# PowerSocket.net
KiCad netlist of a schematic drawn in EAGLE
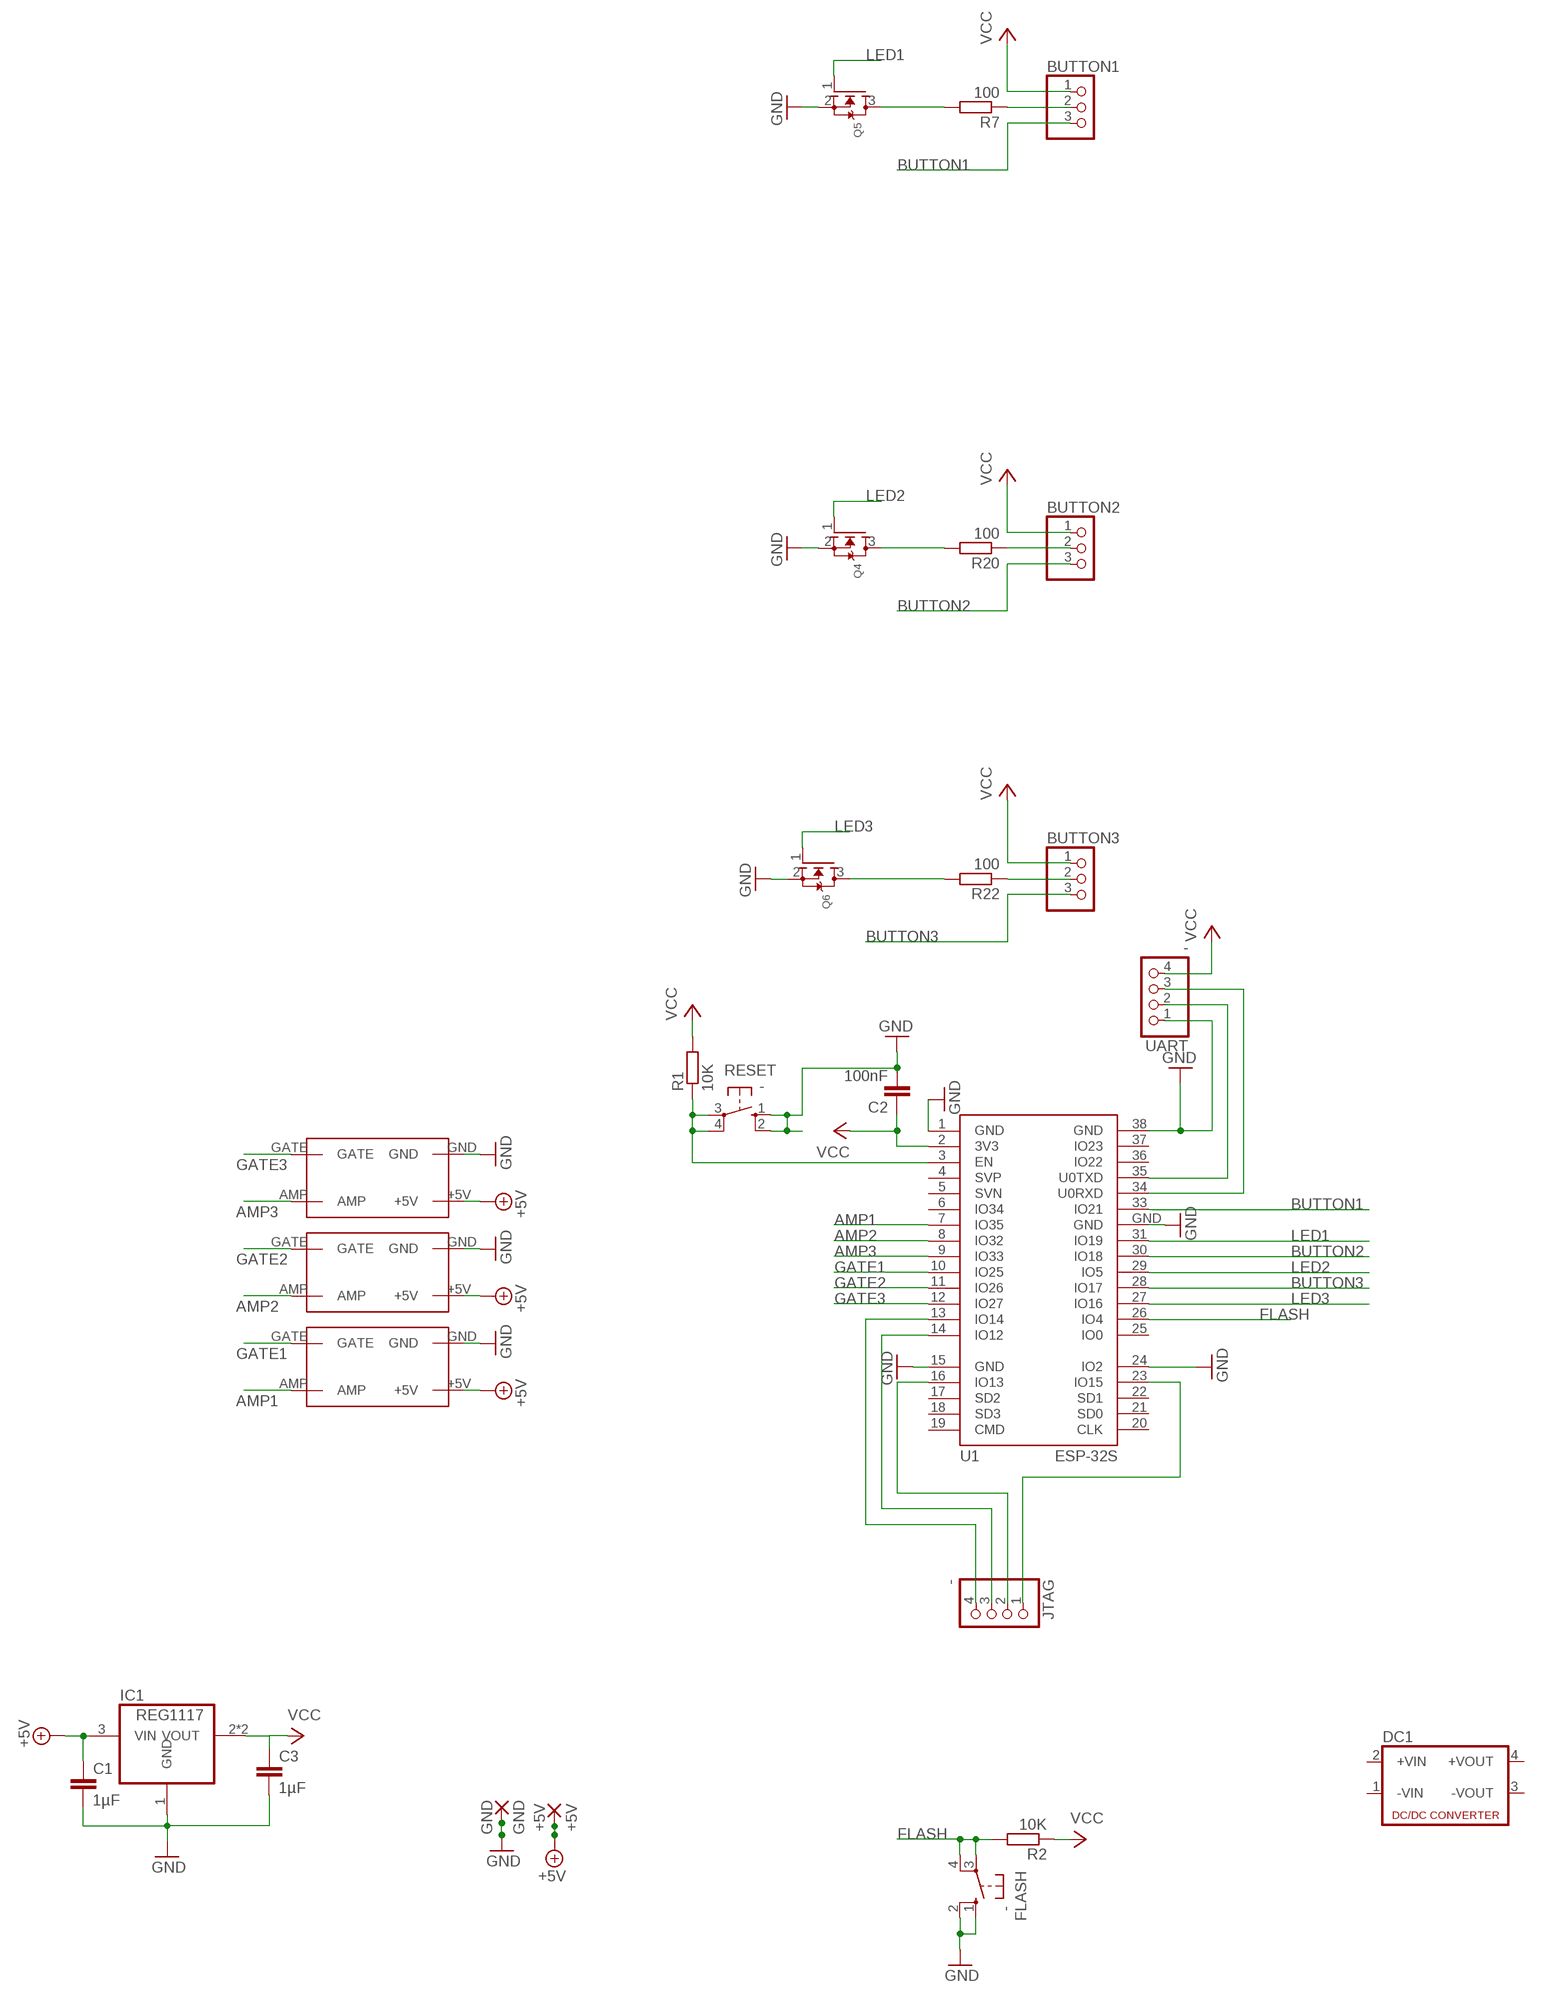
[diagram p0: schematic, sheet 1]

(export (version "E")
  (design (tool "Eeschema 10.0.6"))
  (components
    (comp (ref "+5V")
      (value "+5V")
      (footprint "eagle-import:2,15_1,0")
      (libsource (lib "eagle-import") (part "2,15/1,0"))
    )
    (comp (ref "BUTTON1")
      (value "PINHD-1X3")
      (footprint "eagle-import:1X03")
      (libsource (lib "eagle-import") (part "PINHD-1X3"))
    )
    (comp (ref "BUTTON2")
      (value "PINHD-1X3")
      (footprint "eagle-import:1X03")
      (libsource (lib "eagle-import") (part "PINHD-1X3"))
    )
    (comp (ref "BUTTON3")
      (value "PINHD-1X3")
      (footprint "eagle-import:1X03")
      (libsource (lib "eagle-import") (part "PINHD-1X3"))
    )
    (comp (ref "C1")
      (value "1µF")
      (footprint "eagle-import:C025-024X044")
      (libsource (lib "eagle-import") (part "C-EU025-024X044"))
    )
    (comp (ref "C2")
      (value "100nF")
      (footprint "eagle-import:C1206")
      (libsource (lib "eagle-import") (part "C-EUC1206"))
    )
    (comp (ref "C3")
      (value "1µF")
      (footprint "eagle-import:C025-024X044")
      (libsource (lib "eagle-import") (part "C-EU025-024X044"))
    )
    (comp (ref "DC1")
      (value "NME")
      (footprint "eagle-import:NME")
      (fields (field (name "MF") "C & D TECHNOLOGIES, INC") (field (name "MPN") "NME1205D"))
      (libsource (lib "eagle-import") (part "NME"))
    )
    (comp (ref "FLASH")
      (value "-")
      (footprint "eagle-import:B3F-10XX")
      (fields (field (name "MPN") "B3F-1000"))
      (libsource (lib "eagle-import") (part "10-XX"))
    )
    (comp (ref "GND")
      (value "GND")
      (footprint "eagle-import:2,15_1,0")
      (libsource (lib "eagle-import") (part "2,15/1,0"))
    )
    (comp (ref "IC1")
      (value "REG1117")
      (footprint "eagle-import:SOT223")
      (libsource (lib "eagle-import") (part "REG1117"))
    )
    (comp (ref "JTAG")
      (value "-")
      (footprint "eagle-import:1X04")
      (libsource (lib "eagle-import") (part "PINHD-1X4"))
    )
    (comp (ref "Q4")
      (value "MOSFET-NREFLOW")
      (footprint "eagle-import:SOT23")
      (libsource (lib "eagle-import") (part "MOSFET-NREFLOW"))
    )
    (comp (ref "Q5")
      (value "MOSFET-NREFLOW")
      (footprint "eagle-import:SOT23")
      (libsource (lib "eagle-import") (part "MOSFET-NREFLOW"))
    )
    (comp (ref "Q6")
      (value "MOSFET-NREFLOW")
      (footprint "eagle-import:SOT23")
      (libsource (lib "eagle-import") (part "MOSFET-NREFLOW"))
    )
    (comp (ref "R1")
      (value "10K")
      (footprint "eagle-import:R0805")
      (libsource (lib "eagle-import") (part "R-EU_R0805"))
    )
    (comp (ref "R2")
      (value "10K")
      (footprint "eagle-import:R0805")
      (libsource (lib "eagle-import") (part "R-EU_R0805"))
    )
    (comp (ref "R7")
      (value "100")
      (footprint "eagle-import:R0805")
      (libsource (lib "eagle-import") (part "R-EU_R0805"))
    )
    (comp (ref "R20")
      (value "100")
      (footprint "eagle-import:R0805")
      (libsource (lib "eagle-import") (part "R-EU_R0805"))
    )
    (comp (ref "R22")
      (value "100")
      (footprint "eagle-import:R0805")
      (libsource (lib "eagle-import") (part "R-EU_R0805"))
    )
    (comp (ref "RESET")
      (value "-")
      (footprint "eagle-import:B3F-10XX")
      (fields (field (name "MPN") "B3F-1000"))
      (libsource (lib "eagle-import") (part "10-XX"))
    )
    (comp (ref "U$2")
      (value "RELAY_BOARD")
      (footprint "eagle-import:RELAY_BOARD")
      (libsource (lib "eagle-import") (part "RELAY_BOARD"))
    )
    (comp (ref "U$3")
      (value "RELAY_BOARD")
      (footprint "eagle-import:RELAY_BOARD")
      (libsource (lib "eagle-import") (part "RELAY_BOARD"))
    )
    (comp (ref "U$4")
      (value "RELAY_BOARD")
      (footprint "eagle-import:RELAY_BOARD")
      (libsource (lib "eagle-import") (part "RELAY_BOARD"))
    )
    (comp (ref "U1")
      (value "ESP-32S")
      (footprint "eagle-import:ESP-32S")
      (libsource (lib "eagle-import") (part "ESP-32S"))
    )
    (comp (ref "UART")
      (value "-")
      (footprint "eagle-import:1X04")
      (libsource (lib "eagle-import") (part "PINHD-1X4"))
    )
  )
  (nets
    (net (code "1") (name "+5V") (class "Default")
      (node (ref "+5V") (pin "1") (pinfunction "P_1") (pintype "passive"))
      (node (ref "C1") (pin "1") (pinfunction "1_1") (pintype "passive"))
      (node (ref "IC1") (pin "3") (pinfunction "VIN_3") (pintype "input"))
      (node (ref "U$2") (pin "+5V") (pinfunction "+5V_+5V") (pintype "power_in"))
      (node (ref "U$3") (pin "+5V") (pinfunction "+5V_+5V") (pintype "power_in"))
      (node (ref "U$4") (pin "+5V") (pinfunction "+5V_+5V") (pintype "power_in"))
    )
    (net (code "2") (name "/AMP1") (class "Default")
      (node (ref "U$4") (pin "AMP") (pinfunction "AMP_AMP") (pintype "output"))
      (node (ref "U1") (pin "7") (pinfunction "IO35_7") (pintype "bidirectional"))
    )
    (net (code "3") (name "/AMP2") (class "Default")
      (node (ref "U$3") (pin "AMP") (pinfunction "AMP_AMP") (pintype "output"))
      (node (ref "U1") (pin "8") (pinfunction "IO32_8") (pintype "bidirectional"))
    )
    (net (code "4") (name "/AMP3") (class "Default")
      (node (ref "U$2") (pin "AMP") (pinfunction "AMP_AMP") (pintype "output"))
      (node (ref "U1") (pin "9") (pinfunction "IO33_9") (pintype "bidirectional"))
    )
    (net (code "5") (name "/BUTTON1") (class "Default")
      (node (ref "BUTTON1") (pin "3") (pinfunction "3_3") (pintype "passive"))
      (node (ref "U1") (pin "33") (pinfunction "IO21_33") (pintype "bidirectional"))
    )
    (net (code "6") (name "/BUTTON2") (class "Default")
      (node (ref "BUTTON2") (pin "3") (pinfunction "3_3") (pintype "passive"))
      (node (ref "U1") (pin "30") (pinfunction "IO18_30") (pintype "bidirectional"))
    )
    (net (code "7") (name "/BUTTON3") (class "Default")
      (node (ref "BUTTON3") (pin "3") (pinfunction "3_3") (pintype "passive"))
      (node (ref "U1") (pin "28") (pinfunction "IO17_28") (pintype "bidirectional"))
    )
    (net (code "8") (name "/FLASH") (class "Default")
      (node (ref "FLASH") (pin "3") (pinfunction "P_3") (pintype "passive"))
      (node (ref "FLASH") (pin "4") (pinfunction "P1_4") (pintype "passive"))
      (node (ref "R2") (pin "2") (pinfunction "2_2") (pintype "passive"))
      (node (ref "U1") (pin "26") (pinfunction "IO4_26") (pintype "bidirectional"))
    )
    (net (code "9") (name "/GATE1") (class "Default")
      (node (ref "U$4") (pin "GATE") (pinfunction "GATE_GATE") (pintype "input"))
      (node (ref "U1") (pin "10") (pinfunction "IO25_10") (pintype "bidirectional"))
    )
    (net (code "10") (name "/GATE2") (class "Default")
      (node (ref "U$3") (pin "GATE") (pinfunction "GATE_GATE") (pintype "input"))
      (node (ref "U1") (pin "11") (pinfunction "IO26_11") (pintype "bidirectional"))
    )
    (net (code "11") (name "/GATE3") (class "Default")
      (node (ref "U$2") (pin "GATE") (pinfunction "GATE_GATE") (pintype "input"))
      (node (ref "U1") (pin "12") (pinfunction "IO27_12") (pintype "bidirectional"))
    )
    (net (code "12") (name "/LED1") (class "Default")
      (node (ref "Q5") (pin "1") (pinfunction "G_1") (pintype "bidirectional"))
      (node (ref "U1") (pin "31") (pinfunction "IO19_31") (pintype "bidirectional"))
    )
    (net (code "13") (name "/LED2") (class "Default")
      (node (ref "Q4") (pin "1") (pinfunction "G_1") (pintype "bidirectional"))
      (node (ref "U1") (pin "29") (pinfunction "IO5_29") (pintype "bidirectional"))
    )
    (net (code "14") (name "/LED3") (class "Default")
      (node (ref "Q6") (pin "1") (pinfunction "G_1") (pintype "bidirectional"))
      (node (ref "U1") (pin "27") (pinfunction "IO16_27") (pintype "bidirectional"))
    )
    (net (code "15") (name "GND") (class "Default")
      (node (ref "C1") (pin "2") (pinfunction "2_2") (pintype "passive"))
      (node (ref "C2") (pin "2") (pinfunction "2_2") (pintype "passive"))
      (node (ref "C3") (pin "2") (pinfunction "2_2") (pintype "passive"))
      (node (ref "FLASH") (pin "1") (pinfunction "S_1") (pintype "passive"))
      (node (ref "FLASH") (pin "2") (pinfunction "S1_2") (pintype "passive"))
      (node (ref "GND") (pin "1") (pinfunction "P_1") (pintype "passive"))
      (node (ref "IC1") (pin "1") (pinfunction "GND_1") (pintype "power_in"))
      (node (ref "Q4") (pin "2") (pinfunction "S_2") (pintype "bidirectional"))
      (node (ref "Q5") (pin "2") (pinfunction "S_2") (pintype "bidirectional"))
      (node (ref "Q6") (pin "2") (pinfunction "S_2") (pintype "bidirectional"))
      (node (ref "RESET") (pin "1") (pinfunction "S_1") (pintype "passive"))
      (node (ref "RESET") (pin "2") (pinfunction "S1_2") (pintype "passive"))
      (node (ref "U$2") (pin "GND") (pinfunction "GND_GND") (pintype "power_in"))
      (node (ref "U$3") (pin "GND") (pinfunction "GND_GND") (pintype "power_in"))
      (node (ref "U$4") (pin "GND") (pinfunction "GND_GND") (pintype "power_in"))
      (node (ref "U1") (pin "1") (pinfunction "GND_1") (pintype "power_in"))
      (node (ref "U1") (pin "15") (pinfunction "GND_15") (pintype "power_in"))
      (node (ref "U1") (pin "24") (pinfunction "IO2_24") (pintype "bidirectional"))
      (node (ref "U1") (pin "38") (pinfunction "GND_38") (pintype "power_in"))
      (node (ref "U1") (pin "GND") (pinfunction "GND_GND") (pintype "power_in"))
      (node (ref "UART") (pin "1") (pinfunction "1_1") (pintype "passive"))
    )
    (net (code "16") (name "Net-(BUTTON1-Pad2)") (class "Default")
      (node (ref "BUTTON1") (pin "2") (pinfunction "2_2") (pintype "passive"))
      (node (ref "R7") (pin "1") (pinfunction "1_1") (pintype "passive"))
    )
    (net (code "17") (name "Net-(BUTTON2-Pad2)") (class "Default")
      (node (ref "BUTTON2") (pin "2") (pinfunction "2_2") (pintype "passive"))
      (node (ref "R20") (pin "1") (pinfunction "1_1") (pintype "passive"))
    )
    (net (code "18") (name "Net-(BUTTON3-Pad2)") (class "Default")
      (node (ref "BUTTON3") (pin "2") (pinfunction "2_2") (pintype "passive"))
      (node (ref "R22") (pin "1") (pinfunction "1_1") (pintype "passive"))
    )
    (net (code "19") (name "Net-(Q4-D)") (class "Default")
      (node (ref "Q4") (pin "3") (pinfunction "D_3") (pintype "bidirectional"))
      (node (ref "R20") (pin "2") (pinfunction "2_2") (pintype "passive"))
    )
    (net (code "20") (name "Net-(Q5-D)") (class "Default")
      (node (ref "Q5") (pin "3") (pinfunction "D_3") (pintype "bidirectional"))
      (node (ref "R7") (pin "2") (pinfunction "2_2") (pintype "passive"))
    )
    (net (code "21") (name "Net-(Q6-D)") (class "Default")
      (node (ref "Q6") (pin "3") (pinfunction "D_3") (pintype "bidirectional"))
      (node (ref "R22") (pin "2") (pinfunction "2_2") (pintype "passive"))
    )
    (net (code "22") (name "Net-(RESET-P)") (class "Default")
      (node (ref "R1") (pin "1") (pinfunction "1_1") (pintype "passive"))
      (node (ref "RESET") (pin "3") (pinfunction "P_3") (pintype "passive"))
      (node (ref "RESET") (pin "4") (pinfunction "P1_4") (pintype "passive"))
      (node (ref "U1") (pin "3") (pinfunction "EN_3") (pintype "input"))
    )
    (net (code "23") (name "Net-(U1-IO12)") (class "Default")
      (node (ref "JTAG") (pin "3") (pinfunction "3_3") (pintype "passive"))
      (node (ref "U1") (pin "14") (pinfunction "IO12_14") (pintype "bidirectional"))
    )
    (net (code "24") (name "Net-(U1-IO13)") (class "Default")
      (node (ref "JTAG") (pin "2") (pinfunction "2_2") (pintype "passive"))
      (node (ref "U1") (pin "16") (pinfunction "IO13_16") (pintype "bidirectional"))
    )
    (net (code "25") (name "Net-(U1-IO14)") (class "Default")
      (node (ref "JTAG") (pin "4") (pinfunction "4_4") (pintype "passive"))
      (node (ref "U1") (pin "13") (pinfunction "IO14_13") (pintype "bidirectional"))
    )
    (net (code "26") (name "Net-(U1-IO15)") (class "Default")
      (node (ref "JTAG") (pin "1") (pinfunction "1_1") (pintype "passive"))
      (node (ref "U1") (pin "23") (pinfunction "IO15_23") (pintype "bidirectional"))
    )
    (net (code "27") (name "Net-(U1-U0RXD)") (class "Default")
      (node (ref "U1") (pin "34") (pinfunction "U0RXD_34") (pintype "bidirectional"))
      (node (ref "UART") (pin "3") (pinfunction "3_3") (pintype "passive"))
    )
    (net (code "28") (name "Net-(U1-U0TXD)") (class "Default")
      (node (ref "U1") (pin "35") (pinfunction "U0TXD_35") (pintype "bidirectional"))
      (node (ref "UART") (pin "2") (pinfunction "2_2") (pintype "passive"))
    )
    (net (code "29") (name "VCC") (class "Default")
      (node (ref "BUTTON1") (pin "1") (pinfunction "1_1") (pintype "passive"))
      (node (ref "BUTTON2") (pin "1") (pinfunction "1_1") (pintype "passive"))
      (node (ref "BUTTON3") (pin "1") (pinfunction "1_1") (pintype "passive"))
      (node (ref "C2") (pin "1") (pinfunction "1_1") (pintype "passive"))
      (node (ref "C3") (pin "1") (pinfunction "1_1") (pintype "passive"))
      (node (ref "IC1") (pin "2") (pinfunction "VOUT_2") (pintype "output"))
      (node (ref "IC1") (pin "4") (pinfunction "VOUT_4") (pintype "output"))
      (node (ref "R1") (pin "2") (pinfunction "2_2") (pintype "passive"))
      (node (ref "R2") (pin "1") (pinfunction "1_1") (pintype "passive"))
      (node (ref "U1") (pin "2") (pinfunction "3V3_2") (pintype "power_in"))
      (node (ref "UART") (pin "4") (pinfunction "4_4") (pintype "passive"))
    )
    (net (code "30") (name "unconnected-(DC1-+VIN-Pad2)") (class "Default")
      (node (ref "DC1") (pin "2") (pinfunction "+VIN_2") (pintype "passive"))
    )
    (net (code "31") (name "unconnected-(DC1-+VOUT-Pad4)") (class "Default")
      (node (ref "DC1") (pin "4") (pinfunction "+VOUT_4") (pintype "passive"))
    )
    (net (code "32") (name "unconnected-(DC1--VIN-Pad1)") (class "Default")
      (node (ref "DC1") (pin "1") (pinfunction "-VIN_1") (pintype "passive"))
    )
    (net (code "33") (name "unconnected-(DC1--VOUT-Pad3)") (class "Default")
      (node (ref "DC1") (pin "3") (pinfunction "-VOUT_3") (pintype "passive"))
    )
    (net (code "34") (name "unconnected-(U1-CLK-Pad20)") (class "Default")
      (node (ref "U1") (pin "20") (pinfunction "CLK_20") (pintype "bidirectional"))
    )
    (net (code "35") (name "unconnected-(U1-CMD-Pad19)") (class "Default")
      (node (ref "U1") (pin "19") (pinfunction "CMD_19") (pintype "bidirectional"))
    )
    (net (code "36") (name "unconnected-(U1-IO0-Pad25)") (class "Default")
      (node (ref "U1") (pin "25") (pinfunction "IO0_25") (pintype "bidirectional"))
    )
    (net (code "37") (name "unconnected-(U1-IO22-Pad36)") (class "Default")
      (node (ref "U1") (pin "36") (pinfunction "IO22_36") (pintype "bidirectional"))
    )
    (net (code "38") (name "unconnected-(U1-IO23-Pad37)") (class "Default")
      (node (ref "U1") (pin "37") (pinfunction "IO23_37") (pintype "bidirectional"))
    )
    (net (code "39") (name "unconnected-(U1-IO34-Pad6)") (class "Default")
      (node (ref "U1") (pin "6") (pinfunction "IO34_6") (pintype "bidirectional"))
    )
    (net (code "40") (name "unconnected-(U1-SD0-Pad21)") (class "Default")
      (node (ref "U1") (pin "21") (pinfunction "SD0_21") (pintype "bidirectional"))
    )
    (net (code "41") (name "unconnected-(U1-SD1-Pad22)") (class "Default")
      (node (ref "U1") (pin "22") (pinfunction "SD1_22") (pintype "bidirectional"))
    )
    (net (code "42") (name "unconnected-(U1-SD2-Pad17)") (class "Default")
      (node (ref "U1") (pin "17") (pinfunction "SD2_17") (pintype "bidirectional"))
    )
    (net (code "43") (name "unconnected-(U1-SD3-Pad18)") (class "Default")
      (node (ref "U1") (pin "18") (pinfunction "SD3_18") (pintype "bidirectional"))
    )
    (net (code "44") (name "unconnected-(U1-SVN-Pad5)") (class "Default")
      (node (ref "U1") (pin "5") (pinfunction "SVN_5") (pintype "bidirectional"))
    )
    (net (code "45") (name "unconnected-(U1-SVP-Pad4)") (class "Default")
      (node (ref "U1") (pin "4") (pinfunction "SVP_4") (pintype "bidirectional"))
    )
  )
)
